# minnowboard-to-busblaster.net
KiCad netlist of a schematic drawn in EAGLE
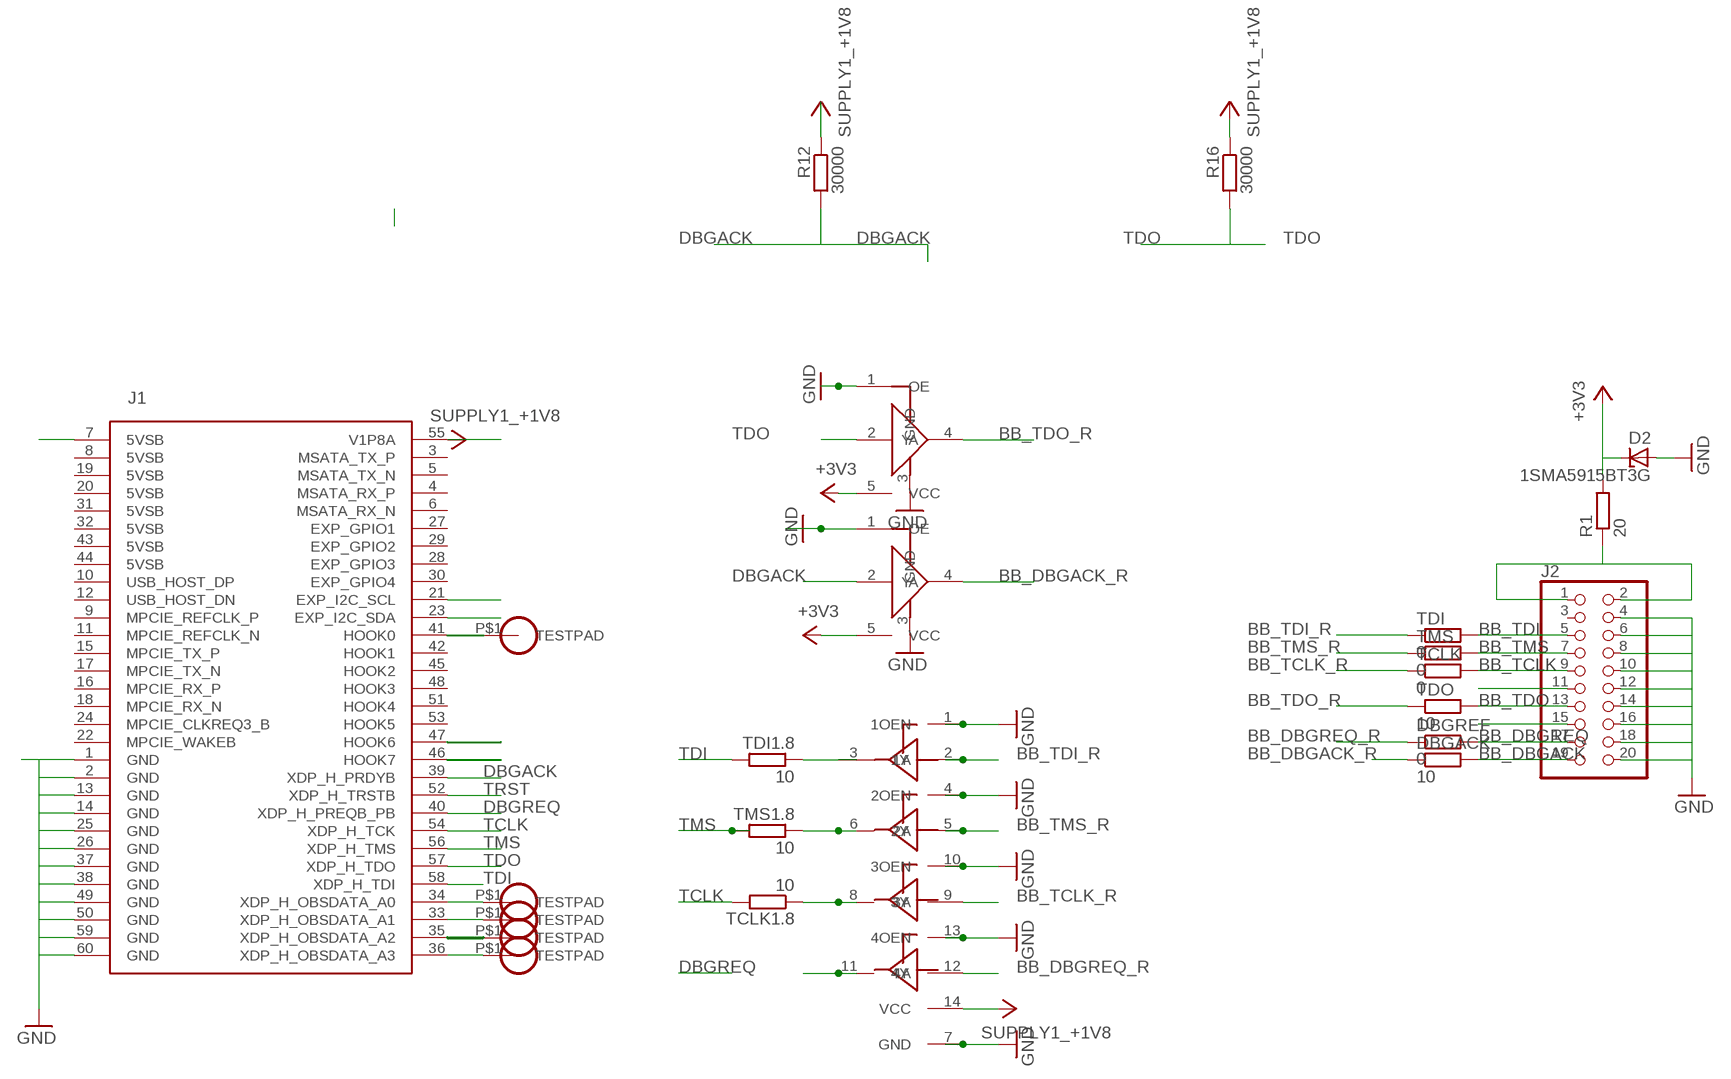
[diagram p0: schematic, sheet 1]

(export (version "E")
  (design (tool "Eeschema 10.0.6"))
  (components
    (comp (ref "A0")
      (value "TESTPAD")
      (footprint "eagle-import:TESTPAD")
      (libsource (lib "eagle-import") (part "TESTPAD"))
    )
    (comp (ref "A1")
      (value "TESTPAD")
      (footprint "eagle-import:TESTPAD")
      (libsource (lib "eagle-import") (part "TESTPAD"))
    )
    (comp (ref "A2")
      (value "TESTPAD")
      (footprint "eagle-import:TESTPAD")
      (libsource (lib "eagle-import") (part "TESTPAD"))
    )
    (comp (ref "A3")
      (value "TESTPAD")
      (footprint "eagle-import:TESTPAD")
      (libsource (lib "eagle-import") (part "TESTPAD"))
    )
    (comp (ref "D2")
      (value "1SMA5915BT3G")
      (footprint "eagle-import:DIODE_SMB")
      (libsource (lib "eagle-import") (part "DIODE_ZENER-DIODESMB"))
    )
    (comp (ref "DBGACK")
      (value "10")
      (footprint "eagle-import:R0805")
      (libsource (lib "eagle-import") (part "R-EU_R0805"))
    )
    (comp (ref "DBGREF")
      (value "0")
      (footprint "eagle-import:R0805")
      (libsource (lib "eagle-import") (part "R-EU_R0805"))
    )
    (comp (ref "J1")
      (value "CIRCUITCO_MINNOW2_HIGH_SPEED")
      (footprint "eagle-import:CIRCUITCO_5177986-2")
      (libsource (lib "eagle-import") (part "CIRCUITCO_MINNOW2_HIGH_SPEED"))
    )
    (comp (ref "J2")
      (value "LPC1768BOARD_PINHEAD_-_COPY_PINHD-2X10SHROUDED")
      (footprint "eagle-import:LPC1768BOARD_PINHEAD_-_COPY_PINSHRD_PTH_2X10")
      (libsource (lib "eagle-import") (part "LPC1768BOARD_PINHEAD_-_COPY_PINHD-2X10SHROUDED"))
    )
    (comp (ref "R1")
      (value "20")
      (footprint "eagle-import:R0805")
      (libsource (lib "eagle-import") (part "R-EU_R0805"))
    )
    (comp (ref "R12")
      (value "30000")
      (footprint "eagle-import:R0805")
      (libsource (lib "eagle-import") (part "R-EU_R0805"))
    )
    (comp (ref "R16")
      (value "30000")
      (footprint "eagle-import:R0805")
      (libsource (lib "eagle-import") (part "R-EU_R0805"))
    )
    (comp (ref "TCLK")
      (value "0")
      (footprint "eagle-import:R0805")
      (libsource (lib "eagle-import") (part "R-EU_R0805"))
    )
    (comp (ref "TCLK1.8")
      (value "10")
      (footprint "eagle-import:R0805")
      (libsource (lib "eagle-import") (part "R-EU_R0805"))
    )
    (comp (ref "TDI")
      (value "0")
      (footprint "eagle-import:R0805")
      (libsource (lib "eagle-import") (part "R-EU_R0805"))
    )
    (comp (ref "TDI1.8")
      (value "10")
      (footprint "eagle-import:R0805")
      (libsource (lib "eagle-import") (part "R-EU_R0805"))
    )
    (comp (ref "TDO")
      (value "10")
      (footprint "eagle-import:R0805")
      (libsource (lib "eagle-import") (part "R-EU_R0805"))
    )
    (comp (ref "TMS")
      (value "0")
      (footprint "eagle-import:R0805")
      (libsource (lib "eagle-import") (part "R-EU_R0805"))
    )
    (comp (ref "TMS1.8")
      (value "10")
      (footprint "eagle-import:R0805")
      (libsource (lib "eagle-import") (part "R-EU_R0805"))
    )
    (comp (ref "U$1")
      (value "TESTPAD")
      (footprint "eagle-import:TESTPAD")
      (libsource (lib "eagle-import") (part "TESTPAD"))
    )
    (comp (ref "U1")
      (value "SN74LV4T125")
      (footprint "eagle-import:PVQFN-N14")
      (libsource (lib "eagle-import") (part "SN74LV4T125"))
    )
    (comp (ref "U2")
      (value "SN74LV1T125")
      (footprint "eagle-import:SC70-5")
      (libsource (lib "eagle-import") (part "SN74LV1T125"))
    )
    (comp (ref "U3")
      (value "SN74LV1T125")
      (footprint "eagle-import:SC70-5")
      (libsource (lib "eagle-import") (part "SN74LV1T125"))
    )
  )
  (nets
    (net (code "1") (name "+3V3") (class "Default")
      (node (ref "D2") (pin "C") (pinfunction "C_C") (pintype "passive"))
      (node (ref "R1") (pin "2") (pinfunction "2_2") (pintype "passive"))
      (node (ref "U2") (pin "5") (pinfunction "VCC_5") (pintype "bidirectional"))
      (node (ref "U3") (pin "5") (pinfunction "VCC_5") (pintype "bidirectional"))
    )
    (net (code "2") (name "/BB_DBGACK") (class "Default")
      (node (ref "DBGACK") (pin "2") (pinfunction "2_2") (pintype "passive"))
      (node (ref "J2") (pin "19") (pinfunction "19_19") (pintype "passive"))
    )
    (net (code "3") (name "/BB_DBGACK_R") (class "Default")
      (node (ref "DBGACK") (pin "1") (pinfunction "1_1") (pintype "passive"))
      (node (ref "U2") (pin "4") (pinfunction "Y_4") (pintype "bidirectional"))
    )
    (net (code "4") (name "/BB_DBGREQ") (class "Default")
      (node (ref "DBGREF") (pin "2") (pinfunction "2_2") (pintype "passive"))
      (node (ref "J2") (pin "17") (pinfunction "17_17") (pintype "passive"))
    )
    (net (code "5") (name "/BB_DBGREQ_R") (class "Default")
      (node (ref "DBGREF") (pin "1") (pinfunction "1_1") (pintype "passive"))
      (node (ref "U1") (pin "12") (pinfunction "4A_12") (pintype "bidirectional"))
    )
    (net (code "6") (name "/BB_TCLK") (class "Default")
      (node (ref "J2") (pin "9") (pinfunction "9_9") (pintype "passive"))
      (node (ref "TCLK") (pin "2") (pinfunction "2_2") (pintype "passive"))
    )
    (net (code "7") (name "/BB_TCLK_R") (class "Default")
      (node (ref "TCLK") (pin "1") (pinfunction "1_1") (pintype "passive"))
      (node (ref "U1") (pin "9") (pinfunction "3A_9") (pintype "bidirectional"))
    )
    (net (code "8") (name "/BB_TDI") (class "Default")
      (node (ref "J2") (pin "5") (pinfunction "5_5") (pintype "passive"))
      (node (ref "TDI") (pin "2") (pinfunction "2_2") (pintype "passive"))
    )
    (net (code "9") (name "/BB_TDI_R") (class "Default")
      (node (ref "TDI") (pin "1") (pinfunction "1_1") (pintype "passive"))
      (node (ref "U1") (pin "2") (pinfunction "1A_2") (pintype "bidirectional"))
    )
    (net (code "10") (name "/BB_TDO") (class "Default")
      (node (ref "J2") (pin "13") (pinfunction "13_13") (pintype "passive"))
      (node (ref "TDO") (pin "2") (pinfunction "2_2") (pintype "passive"))
    )
    (net (code "11") (name "/BB_TDO_R") (class "Default")
      (node (ref "TDO") (pin "1") (pinfunction "1_1") (pintype "passive"))
      (node (ref "U3") (pin "4") (pinfunction "Y_4") (pintype "bidirectional"))
    )
    (net (code "12") (name "/BB_TMS") (class "Default")
      (node (ref "J2") (pin "7") (pinfunction "7_7") (pintype "passive"))
      (node (ref "TMS") (pin "2") (pinfunction "2_2") (pintype "passive"))
    )
    (net (code "13") (name "/BB_TMS_R") (class "Default")
      (node (ref "TMS") (pin "1") (pinfunction "1_1") (pintype "passive"))
      (node (ref "U1") (pin "5") (pinfunction "2A_5") (pintype "bidirectional"))
    )
    (net (code "14") (name "/DBGACK") (class "Default")
      (node (ref "J1") (pin "39") (pinfunction "XDP_H_PRDYB_39") (pintype "bidirectional"))
      (node (ref "R12") (pin "2") (pinfunction "2_2") (pintype "passive"))
      (node (ref "U2") (pin "2") (pinfunction "A_2") (pintype "bidirectional"))
    )
    (net (code "15") (name "/DBGREQ") (class "Default")
      (node (ref "J1") (pin "40") (pinfunction "XDP_H_PREQB_PB_40") (pintype "bidirectional"))
    )
    (net (code "16") (name "/TCLK") (class "Default")
      (node (ref "J1") (pin "54") (pinfunction "XDP_H_TCK_54") (pintype "bidirectional"))
      (node (ref "TCLK1.8") (pin "2") (pinfunction "2_2") (pintype "passive"))
    )
    (net (code "17") (name "/TDI") (class "Default")
      (node (ref "J1") (pin "58") (pinfunction "XDP_H_TDI_58") (pintype "bidirectional"))
      (node (ref "TDI1.8") (pin "2") (pinfunction "2_2") (pintype "passive"))
    )
    (net (code "18") (name "/TDO") (class "Default")
      (node (ref "J1") (pin "57") (pinfunction "XDP_H_TDO_57") (pintype "bidirectional"))
      (node (ref "R16") (pin "2") (pinfunction "2_2") (pintype "passive"))
      (node (ref "U3") (pin "2") (pinfunction "A_2") (pintype "bidirectional"))
    )
    (net (code "19") (name "/TMS") (class "Default")
      (node (ref "J1") (pin "56") (pinfunction "XDP_H_TMS_56") (pintype "bidirectional"))
      (node (ref "TMS1.8") (pin "2") (pinfunction "2_2") (pintype "passive"))
    )
    (net (code "20") (name "/TRST") (class "Default")
      (node (ref "J1") (pin "52") (pinfunction "XDP_H_TRSTB_52") (pintype "bidirectional"))
    )
    (net (code "21") (name "GND") (class "Default")
      (node (ref "D2") (pin "A") (pinfunction "A_A") (pintype "passive"))
      (node (ref "J1") (pin "1") (pinfunction "GND_1") (pintype "bidirectional"))
      (node (ref "J1") (pin "13") (pinfunction "GND_13") (pintype "bidirectional"))
      (node (ref "J1") (pin "14") (pinfunction "GND_14") (pintype "bidirectional"))
      (node (ref "J1") (pin "2") (pinfunction "GND_2") (pintype "bidirectional"))
      (node (ref "J1") (pin "25") (pinfunction "GND_25") (pintype "bidirectional"))
      (node (ref "J1") (pin "26") (pinfunction "GND_26") (pintype "bidirectional"))
      (node (ref "J1") (pin "37") (pinfunction "GND_37") (pintype "bidirectional"))
      (node (ref "J1") (pin "38") (pinfunction "GND_38") (pintype "bidirectional"))
      (node (ref "J1") (pin "49") (pinfunction "GND_49") (pintype "bidirectional"))
      (node (ref "J1") (pin "50") (pinfunction "GND_50") (pintype "bidirectional"))
      (node (ref "J1") (pin "59") (pinfunction "GND_59") (pintype "bidirectional"))
      (node (ref "J1") (pin "60") (pinfunction "GND_60") (pintype "bidirectional"))
      (node (ref "J2") (pin "18") (pinfunction "18_18") (pintype "passive"))
      (node (ref "J2") (pin "20") (pinfunction "20_20") (pintype "passive"))
      (node (ref "J2") (pin "4") (pinfunction "4_4") (pintype "passive"))
      (node (ref "U1") (pin "1") (pinfunction "1OEN_1") (pintype "bidirectional"))
      (node (ref "U1") (pin "10") (pinfunction "3OEN_10") (pintype "bidirectional"))
      (node (ref "U1") (pin "13") (pinfunction "4OEN_13") (pintype "bidirectional"))
      (node (ref "U1") (pin "4") (pinfunction "2OEN_4") (pintype "bidirectional"))
      (node (ref "U1") (pin "7") (pinfunction "GND_7") (pintype "bidirectional"))
      (node (ref "U2") (pin "1") (pinfunction "OE_1") (pintype "bidirectional"))
      (node (ref "U2") (pin "3") (pinfunction "GND_3") (pintype "bidirectional"))
      (node (ref "U3") (pin "1") (pinfunction "OE_1") (pintype "bidirectional"))
      (node (ref "U3") (pin "3") (pinfunction "GND_3") (pintype "bidirectional"))
    )
    (net (code "22") (name "Net-(A0-TESTPAD)") (class "Default")
      (node (ref "A0") (pin "P$1") (pinfunction "TESTPAD_P$1") (pintype "bidirectional"))
      (node (ref "J1") (pin "34") (pinfunction "XDP_H_OBSDATA_A0_34") (pintype "bidirectional"))
    )
    (net (code "23") (name "Net-(A1-TESTPAD)") (class "Default")
      (node (ref "A1") (pin "P$1") (pinfunction "TESTPAD_P$1") (pintype "bidirectional"))
      (node (ref "J1") (pin "33") (pinfunction "XDP_H_OBSDATA_A1_33") (pintype "bidirectional"))
    )
    (net (code "24") (name "Net-(A2-TESTPAD)") (class "Default")
      (node (ref "A2") (pin "P$1") (pinfunction "TESTPAD_P$1") (pintype "bidirectional"))
      (node (ref "J1") (pin "35") (pinfunction "XDP_H_OBSDATA_A2_35") (pintype "bidirectional"))
    )
    (net (code "25") (name "Net-(A3-TESTPAD)") (class "Default")
      (node (ref "A3") (pin "P$1") (pinfunction "TESTPAD_P$1") (pintype "bidirectional"))
      (node (ref "J1") (pin "36") (pinfunction "XDP_H_OBSDATA_A3_36") (pintype "bidirectional"))
    )
    (net (code "26") (name "Net-(J1-HOOK0)") (class "Default")
      (node (ref "J1") (pin "41") (pinfunction "HOOK0_41") (pintype "bidirectional"))
      (node (ref "U$1") (pin "P$1") (pinfunction "TESTPAD_P$1") (pintype "bidirectional"))
    )
    (net (code "27") (name "Net-(J2-Pad1)") (class "Default")
      (node (ref "J2") (pin "1") (pinfunction "1_1") (pintype "passive"))
      (node (ref "J2") (pin "2") (pinfunction "2_2") (pintype "passive"))
      (node (ref "R1") (pin "1") (pinfunction "1_1") (pintype "passive"))
    )
    (net (code "28") (name "Net-(U1-1Y)") (class "Default")
      (node (ref "TDI1.8") (pin "1") (pinfunction "1_1") (pintype "passive"))
      (node (ref "U1") (pin "3") (pinfunction "1Y_3") (pintype "bidirectional"))
    )
    (net (code "29") (name "Net-(U1-2Y)") (class "Default")
      (node (ref "TMS1.8") (pin "1") (pinfunction "1_1") (pintype "passive"))
      (node (ref "U1") (pin "6") (pinfunction "2Y_6") (pintype "bidirectional"))
    )
    (net (code "30") (name "Net-(U1-3Y)") (class "Default")
      (node (ref "TCLK1.8") (pin "1") (pinfunction "1_1") (pintype "passive"))
      (node (ref "U1") (pin "8") (pinfunction "3Y_8") (pintype "bidirectional"))
    )
    (net (code "31") (name "SUPPLY1_+1V8") (class "Default")
      (node (ref "J1") (pin "55") (pinfunction "V1P8A_55") (pintype "bidirectional"))
      (node (ref "R12") (pin "1") (pinfunction "1_1") (pintype "passive"))
      (node (ref "R16") (pin "1") (pinfunction "1_1") (pintype "passive"))
      (node (ref "U1") (pin "14") (pinfunction "VCC_14") (pintype "bidirectional"))
    )
    (net (code "32") (name "unconnected-(J1-5VSB-Pad7)") (class "Default")
      (node (ref "J1") (pin "7") (pinfunction "5VSB_7") (pintype "bidirectional"))
    )
    (net (code "33") (name "unconnected-(J1-5VSB-Pad8)") (class "Default")
      (node (ref "J1") (pin "8") (pinfunction "5VSB_8") (pintype "bidirectional"))
    )
    (net (code "34") (name "unconnected-(J1-5VSB-Pad19)") (class "Default")
      (node (ref "J1") (pin "19") (pinfunction "5VSB_19") (pintype "bidirectional"))
    )
    (net (code "35") (name "unconnected-(J1-5VSB-Pad20)") (class "Default")
      (node (ref "J1") (pin "20") (pinfunction "5VSB_20") (pintype "bidirectional"))
    )
    (net (code "36") (name "unconnected-(J1-5VSB-Pad31)") (class "Default")
      (node (ref "J1") (pin "31") (pinfunction "5VSB_31") (pintype "bidirectional"))
    )
    (net (code "37") (name "unconnected-(J1-5VSB-Pad32)") (class "Default")
      (node (ref "J1") (pin "32") (pinfunction "5VSB_32") (pintype "bidirectional"))
    )
    (net (code "38") (name "unconnected-(J1-5VSB-Pad43)") (class "Default")
      (node (ref "J1") (pin "43") (pinfunction "5VSB_43") (pintype "bidirectional"))
    )
    (net (code "39") (name "unconnected-(J1-5VSB-Pad44)") (class "Default")
      (node (ref "J1") (pin "44") (pinfunction "5VSB_44") (pintype "bidirectional"))
    )
    (net (code "40") (name "unconnected-(J1-EXP_GPIO1-Pad27)") (class "Default")
      (node (ref "J1") (pin "27") (pinfunction "EXP_GPIO1_27") (pintype "bidirectional"))
    )
    (net (code "41") (name "unconnected-(J1-EXP_GPIO2-Pad29)") (class "Default")
      (node (ref "J1") (pin "29") (pinfunction "EXP_GPIO2_29") (pintype "bidirectional"))
    )
    (net (code "42") (name "unconnected-(J1-EXP_GPIO3-Pad28)") (class "Default")
      (node (ref "J1") (pin "28") (pinfunction "EXP_GPIO3_28") (pintype "bidirectional"))
    )
    (net (code "43") (name "unconnected-(J1-EXP_GPIO4-Pad30)") (class "Default")
      (node (ref "J1") (pin "30") (pinfunction "EXP_GPIO4_30") (pintype "bidirectional"))
    )
    (net (code "44") (name "unconnected-(J1-EXP_I2C_SCL-Pad21)") (class "Default")
      (node (ref "J1") (pin "21") (pinfunction "EXP_I2C_SCL_21") (pintype "bidirectional"))
    )
    (net (code "45") (name "unconnected-(J1-EXP_I2C_SDA-Pad23)") (class "Default")
      (node (ref "J1") (pin "23") (pinfunction "EXP_I2C_SDA_23") (pintype "bidirectional"))
    )
    (net (code "46") (name "unconnected-(J1-HOOK1-Pad42)") (class "Default")
      (node (ref "J1") (pin "42") (pinfunction "HOOK1_42") (pintype "bidirectional"))
    )
    (net (code "47") (name "unconnected-(J1-HOOK2-Pad45)") (class "Default")
      (node (ref "J1") (pin "45") (pinfunction "HOOK2_45") (pintype "bidirectional"))
    )
    (net (code "48") (name "unconnected-(J1-HOOK3-Pad48)") (class "Default")
      (node (ref "J1") (pin "48") (pinfunction "HOOK3_48") (pintype "bidirectional"))
    )
    (net (code "49") (name "unconnected-(J1-HOOK4-Pad51)") (class "Default")
      (node (ref "J1") (pin "51") (pinfunction "HOOK4_51") (pintype "bidirectional"))
    )
    (net (code "50") (name "unconnected-(J1-HOOK5-Pad53)") (class "Default")
      (node (ref "J1") (pin "53") (pinfunction "HOOK5_53") (pintype "bidirectional"))
    )
    (net (code "51") (name "unconnected-(J1-HOOK6-Pad47)") (class "Default")
      (node (ref "J1") (pin "47") (pinfunction "HOOK6_47") (pintype "bidirectional"))
    )
    (net (code "52") (name "unconnected-(J1-HOOK7-Pad46)") (class "Default")
      (node (ref "J1") (pin "46") (pinfunction "HOOK7_46") (pintype "bidirectional"))
    )
    (net (code "53") (name "unconnected-(J1-MPCIE_CLKREQ3_B-Pad24)") (class "Default")
      (node (ref "J1") (pin "24") (pinfunction "MPCIE_CLKREQ3_B_24") (pintype "bidirectional"))
    )
    (net (code "54") (name "unconnected-(J1-MPCIE_REFCLK_N-Pad11)") (class "Default")
      (node (ref "J1") (pin "11") (pinfunction "MPCIE_REFCLK_N_11") (pintype "bidirectional"))
    )
    (net (code "55") (name "unconnected-(J1-MPCIE_REFCLK_P-Pad9)") (class "Default")
      (node (ref "J1") (pin "9") (pinfunction "MPCIE_REFCLK_P_9") (pintype "bidirectional"))
    )
    (net (code "56") (name "unconnected-(J1-MPCIE_RX_N-Pad18)") (class "Default")
      (node (ref "J1") (pin "18") (pinfunction "MPCIE_RX_N_18") (pintype "bidirectional"))
    )
    (net (code "57") (name "unconnected-(J1-MPCIE_RX_P-Pad16)") (class "Default")
      (node (ref "J1") (pin "16") (pinfunction "MPCIE_RX_P_16") (pintype "bidirectional"))
    )
    (net (code "58") (name "unconnected-(J1-MPCIE_TX_N-Pad17)") (class "Default")
      (node (ref "J1") (pin "17") (pinfunction "MPCIE_TX_N_17") (pintype "bidirectional"))
    )
    (net (code "59") (name "unconnected-(J1-MPCIE_TX_P-Pad15)") (class "Default")
      (node (ref "J1") (pin "15") (pinfunction "MPCIE_TX_P_15") (pintype "bidirectional"))
    )
    (net (code "60") (name "unconnected-(J1-MPCIE_WAKEB-Pad22)") (class "Default")
      (node (ref "J1") (pin "22") (pinfunction "MPCIE_WAKEB_22") (pintype "bidirectional"))
    )
    (net (code "61") (name "unconnected-(J1-MSATA_RX_N-Pad6)") (class "Default")
      (node (ref "J1") (pin "6") (pinfunction "MSATA_RX_N_6") (pintype "bidirectional"))
    )
    (net (code "62") (name "unconnected-(J1-MSATA_RX_P-Pad4)") (class "Default")
      (node (ref "J1") (pin "4") (pinfunction "MSATA_RX_P_4") (pintype "bidirectional"))
    )
    (net (code "63") (name "unconnected-(J1-MSATA_TX_N-Pad5)") (class "Default")
      (node (ref "J1") (pin "5") (pinfunction "MSATA_TX_N_5") (pintype "bidirectional"))
    )
    (net (code "64") (name "unconnected-(J1-MSATA_TX_P-Pad3)") (class "Default")
      (node (ref "J1") (pin "3") (pinfunction "MSATA_TX_P_3") (pintype "bidirectional"))
    )
    (net (code "65") (name "unconnected-(J1-USB_HOST_DN-Pad12)") (class "Default")
      (node (ref "J1") (pin "12") (pinfunction "USB_HOST_DN_12") (pintype "bidirectional"))
    )
    (net (code "66") (name "unconnected-(J1-USB_HOST_DP-Pad10)") (class "Default")
      (node (ref "J1") (pin "10") (pinfunction "USB_HOST_DP_10") (pintype "bidirectional"))
    )
    (net (code "67") (name "unconnected-(J2-Pad3)") (class "Default")
      (node (ref "J2") (pin "3") (pinfunction "3_3") (pintype "passive"))
    )
    (net (code "68") (name "unconnected-(J2-Pad6)") (class "Default")
      (node (ref "J2") (pin "6") (pinfunction "6_6") (pintype "passive"))
    )
    (net (code "69") (name "unconnected-(J2-Pad8)") (class "Default")
      (node (ref "J2") (pin "8") (pinfunction "8_8") (pintype "passive"))
    )
    (net (code "70") (name "unconnected-(J2-Pad10)") (class "Default")
      (node (ref "J2") (pin "10") (pinfunction "10_10") (pintype "passive"))
    )
    (net (code "71") (name "unconnected-(J2-Pad11)") (class "Default")
      (node (ref "J2") (pin "11") (pinfunction "11_11") (pintype "passive"))
    )
    (net (code "72") (name "unconnected-(J2-Pad12)") (class "Default")
      (node (ref "J2") (pin "12") (pinfunction "12_12") (pintype "passive"))
    )
    (net (code "73") (name "unconnected-(J2-Pad14)") (class "Default")
      (node (ref "J2") (pin "14") (pinfunction "14_14") (pintype "passive"))
    )
    (net (code "74") (name "unconnected-(J2-Pad15)") (class "Default")
      (node (ref "J2") (pin "15") (pinfunction "15_15") (pintype "passive"))
    )
    (net (code "75") (name "unconnected-(J2-Pad16)") (class "Default")
      (node (ref "J2") (pin "16") (pinfunction "16_16") (pintype "passive"))
    )
    (net (code "76") (name "unconnected-(U1-4Y-Pad11)") (class "Default")
      (node (ref "U1") (pin "11") (pinfunction "4Y_11") (pintype "bidirectional"))
    )
  )
)
